# SCH.net
KiCad netlist of a schematic drawn in Altium Designer
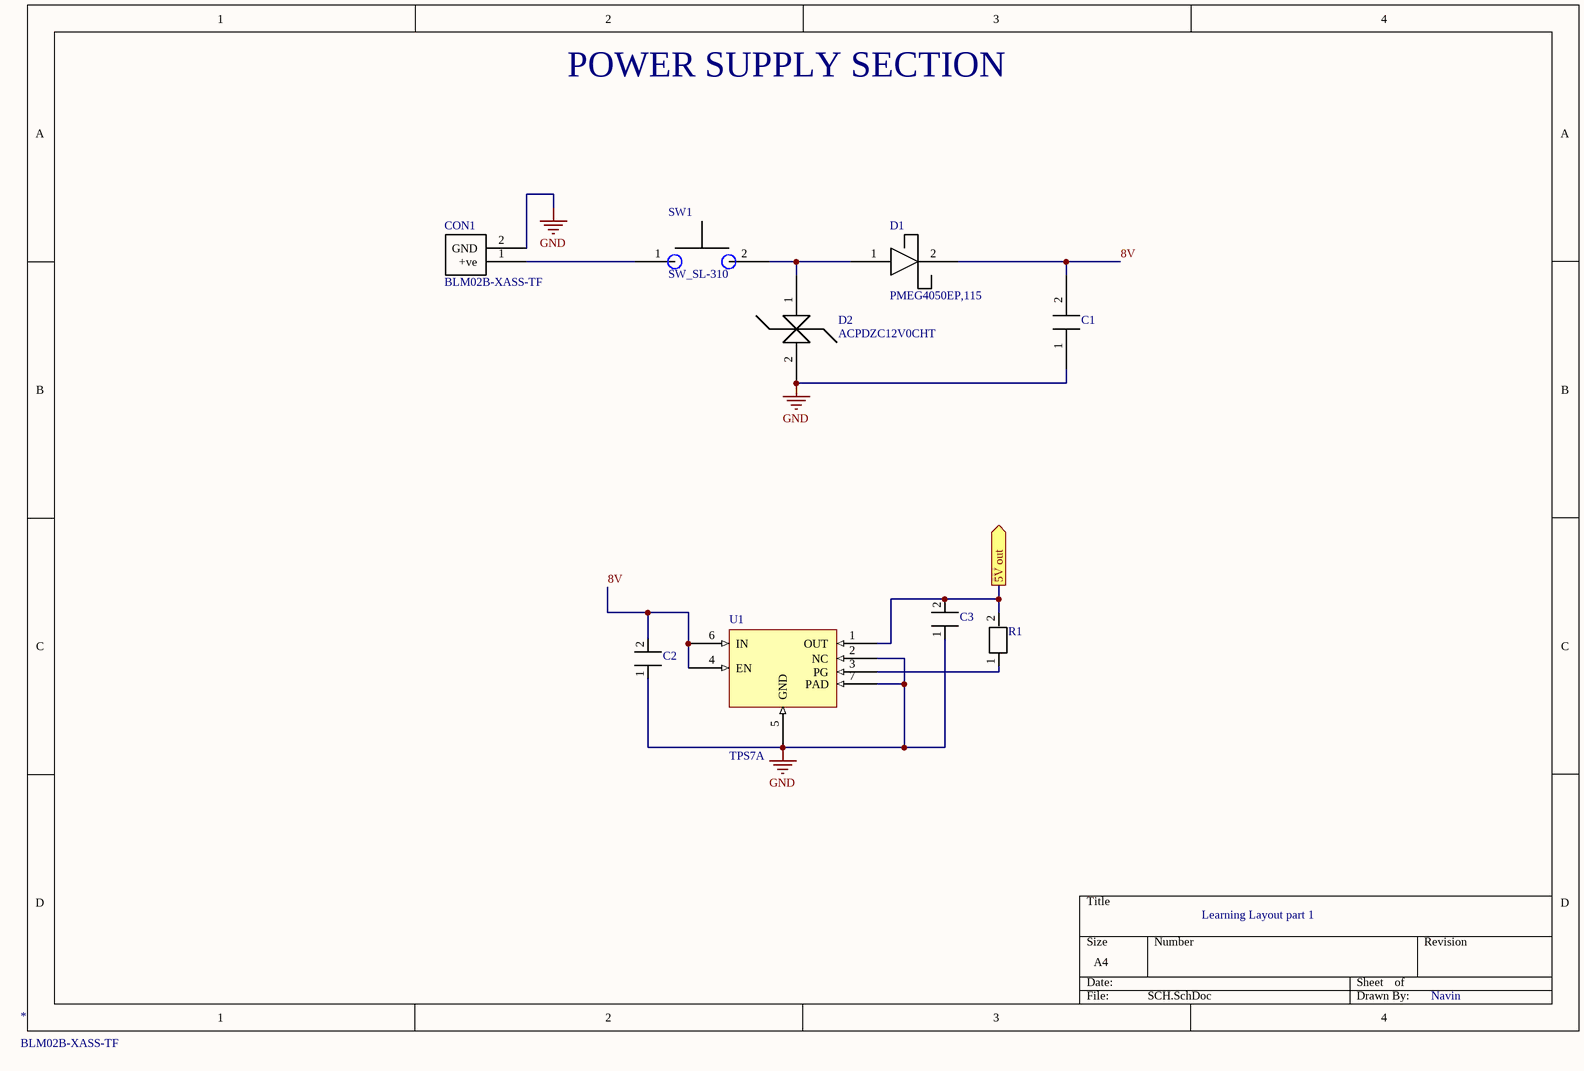
[diagram p0: SCH.SchDoc]

(export (version "E")
  (design (tool "Eeschema 10.0.6"))
  (components
    (comp (ref "*") (value "BLM02B-XASS-TF") (libsource (lib "Schlib1") (part "BLM02B-XASS-TF")))
    (comp (ref "C1")
      (value "~")
      (footprint "3.3F super cap")
      (libsource (lib "Schlib") (part "3.3F super cap"))
    )
    (comp (ref "C2") (value "~") (footprint "3.3F super cap") (libsource (lib "Schlib") (part "Capacitor")))
    (comp (ref "C3") (value "~") (footprint "3.3F super cap") (libsource (lib "Schlib") (part "Capacitor")))
    (comp (ref "CON1")
      (value "BLM02B-XASS-TF")
      (footprint "BM02B-XASS-TF")
      (libsource (lib "Schlib") (part "BLM02B-XASS-TF"))
    )
    (comp (ref "D1")
      (value "PMEG4050EP,115")
      (footprint "PMEG4050 Schottky")
      (libsource (lib "Schlib") (part "PMEG4050EP,115"))
    )
    (comp (ref "D2")
      (value "ACPDZC12V0CHT")
      (footprint "ACPDZC TVS diode")
      (libsource (lib "Schlib") (part "ACPDZC12V0CHT"))
    )
    (comp (ref "R1") (value "~") (libsource (lib "Schlib") (part "Resistor")))
    (comp (ref "SW1")
      (value "SW_SL-310")
      (footprint "SW_SL-310")
      (libsource (lib "Schlib") (part "SW_SL-310"))
    )
    (comp (ref "U1") (value "TPS7A") (footprint "TPS7A") (libsource (lib "Schlib") (part "TPS7A")))
  )
  (nets
    (net (code "1") (name "/5V out") (class "Default")
      (node (ref "C3") (pin "2") (pintype "passive"))
      (node (ref "R1") (pin "2") (pintype "passive"))
      (node (ref "U1") (pin "1") (pinfunction "OUT_1") (pintype "input"))
    )
    (net (code "2") (name "/8V") (class "Default")
      (node (ref "C1") (pin "2") (pintype "passive"))
      (node (ref "C2") (pin "2") (pintype "passive"))
      (node (ref "D1") (pin "2") (pintype "passive"))
      (node (ref "U1") (pin "4") (pinfunction "EN_4") (pintype "input"))
      (node (ref "U1") (pin "6") (pinfunction "IN_6") (pintype "input"))
    )
    (net (code "3") (name "GND") (class "Default")
      (node (ref "C1") (pin "1") (pintype "passive"))
      (node (ref "C2") (pin "1") (pintype "passive"))
      (node (ref "C3") (pin "1") (pintype "passive"))
      (node (ref "CON1") (pin "2") (pinfunction "GND_2") (pintype "passive"))
      (node (ref "D2") (pin "2") (pintype "passive"))
      (node (ref "U1") (pin "2") (pinfunction "NC_2") (pintype "input"))
      (node (ref "U1") (pin "5") (pinfunction "GND_5") (pintype "input"))
      (node (ref "U1") (pin "7") (pinfunction "PAD_7") (pintype "input"))
    )
    (net (code "4") (name "Net-(CON1-+ve)") (class "Default")
      (node (ref "CON1") (pin "1") (pinfunction "+ve_1") (pintype "passive"))
      (node (ref "SW1") (pin "1") (pintype "passive"))
    )
    (net (code "5") (name "Net-(D1-Pad1)") (class "Default")
      (node (ref "D1") (pin "1") (pintype "passive"))
      (node (ref "D2") (pin "1") (pintype "passive"))
      (node (ref "SW1") (pin "2") (pintype "passive"))
    )
    (net (code "6") (name "Net-(U1-PG)") (class "Default")
      (node (ref "R1") (pin "1") (pintype "passive"))
      (node (ref "U1") (pin "3") (pinfunction "PG_3") (pintype "input"))
    )
  )
)
